# eps_pex.net
KiCad netlist of a schematic drawn in Altium Designer
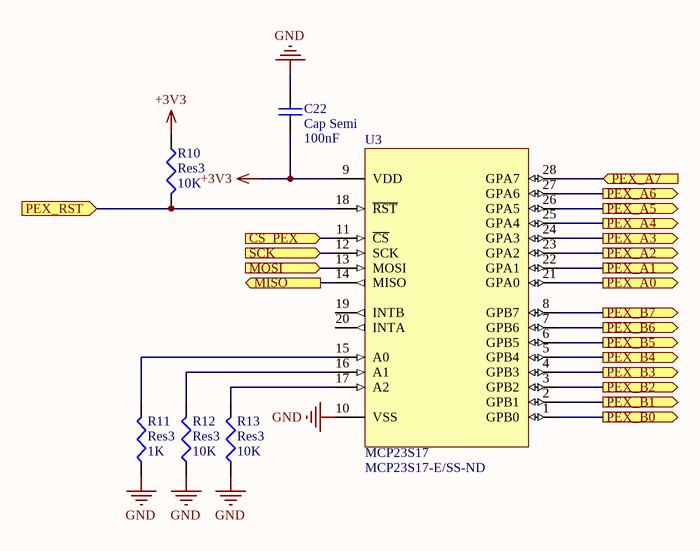
[diagram p0: eps_pex.SchDoc]

(export (version "E")
  (design (tool "Eeschema 10.0.6"))
  (components
    (comp (ref "C22")
      (value "Cap Semi")
      (footprint "1608[0603]")
      (description "Capacitor (Semiconductor SIM Model)")
      (fields (field (name "ALTIUM_VALUE") "100nF") (field (name "PUBLISHER") "Altium Limited"))
      (libsource (lib "Miscellaneous Devices") (part "Cap Semi"))
    )
    (comp (ref "R10")
      (value "Res3")
      (footprint "J1-0603")
      (description "Resistor")
      (fields (field (name "ALTIUM_VALUE") "10K") (field (name "PUBLISHER") "Altium Limited"))
      (libsource (lib "Miscellaneous Devices") (part "Res3"))
    )
    (comp (ref "R11")
      (value "Res3")
      (footprint "J1-0603")
      (description "Resistor")
      (fields (field (name "ALTIUM_VALUE") "1K") (field (name "PUBLISHER") "Altium Limited"))
      (libsource (lib "Miscellaneous Devices") (part "Res3"))
    )
    (comp (ref "R12")
      (value "Res3")
      (footprint "J1-0603")
      (description "Resistor")
      (fields (field (name "ALTIUM_VALUE") "10K") (field (name "PUBLISHER") "Altium Limited"))
      (libsource (lib "Miscellaneous Devices") (part "Res3"))
    )
    (comp (ref "R13")
      (value "Res3")
      (footprint "J1-0603")
      (description "Resistor")
      (fields (field (name "ALTIUM_VALUE") "10K") (field (name "PUBLISHER") "Altium Limited"))
      (libsource (lib "Miscellaneous Devices") (part "Res3"))
    )
    (comp (ref "U3")
      (value "MCP23S17")
      (footprint "SOP65P780X200-28N")
      (description "16 bit I/O expander with SPI interface.")
      (fields (field (name "SUPPLIER PART NUMBER 1") "MCP23S17-E/SS-ND"))
      (libsource (lib "heron-general") (part "MCP23S17"))
    )
  )
  (nets
    (net (code "1") (name "+3V3") (class "Default")
      (node (ref "C22") (pin "2") (pinfunction "2_2") (pintype "passive"))
      (node (ref "R10") (pin "1") (pinfunction "1_1") (pintype "passive"))
      (node (ref "U3") (pin "9") (pinfunction "VDD_9") (pintype "power_in"))
    )
    (net (code "2") (name "/CS_PEX") (class "Default")
      (node (ref "U3") (pin "11") (pinfunction "~{CS}_11") (pintype "input"))
    )
    (net (code "3") (name "/MISO") (class "Default")
      (node (ref "U3") (pin "14") (pinfunction "MISO_14") (pintype "output"))
    )
    (net (code "4") (name "/MOSI") (class "Default")
      (node (ref "U3") (pin "13") (pinfunction "MOSI_13") (pintype "input"))
    )
    (net (code "5") (name "/PEX_A0") (class "Default")
      (node (ref "U3") (pin "21") (pinfunction "GPA0_21") (pintype "bidirectional"))
    )
    (net (code "6") (name "/PEX_A1") (class "Default")
      (node (ref "U3") (pin "22") (pinfunction "GPA1_22") (pintype "bidirectional"))
    )
    (net (code "7") (name "/PEX_A2") (class "Default")
      (node (ref "U3") (pin "23") (pinfunction "GPA2_23") (pintype "bidirectional"))
    )
    (net (code "8") (name "/PEX_A3") (class "Default")
      (node (ref "U3") (pin "24") (pinfunction "GPA3_24") (pintype "bidirectional"))
    )
    (net (code "9") (name "/PEX_A4") (class "Default")
      (node (ref "U3") (pin "25") (pinfunction "GPA4_25") (pintype "bidirectional"))
    )
    (net (code "10") (name "/PEX_A5") (class "Default")
      (node (ref "U3") (pin "26") (pinfunction "GPA5_26") (pintype "bidirectional"))
    )
    (net (code "11") (name "/PEX_A6") (class "Default")
      (node (ref "U3") (pin "27") (pinfunction "GPA6_27") (pintype "bidirectional"))
    )
    (net (code "12") (name "/PEX_A7") (class "Default")
      (node (ref "U3") (pin "28") (pinfunction "GPA7_28") (pintype "bidirectional"))
    )
    (net (code "13") (name "/PEX_B0") (class "Default")
      (node (ref "U3") (pin "1") (pinfunction "GPB0_1") (pintype "bidirectional"))
    )
    (net (code "14") (name "/PEX_B1") (class "Default")
      (node (ref "U3") (pin "2") (pinfunction "GPB1_2") (pintype "bidirectional"))
    )
    (net (code "15") (name "/PEX_B2") (class "Default")
      (node (ref "U3") (pin "3") (pinfunction "GPB2_3") (pintype "bidirectional"))
    )
    (net (code "16") (name "/PEX_B3") (class "Default")
      (node (ref "U3") (pin "4") (pinfunction "GPB3_4") (pintype "bidirectional"))
    )
    (net (code "17") (name "/PEX_B4") (class "Default")
      (node (ref "U3") (pin "5") (pinfunction "GPB4_5") (pintype "bidirectional"))
    )
    (net (code "18") (name "/PEX_B5") (class "Default")
      (node (ref "U3") (pin "6") (pinfunction "GPB5_6") (pintype "bidirectional"))
    )
    (net (code "19") (name "/PEX_B6") (class "Default")
      (node (ref "U3") (pin "7") (pinfunction "GPB6_7") (pintype "bidirectional"))
    )
    (net (code "20") (name "/PEX_B7") (class "Default")
      (node (ref "U3") (pin "8") (pinfunction "GPB7_8") (pintype "bidirectional"))
    )
    (net (code "21") (name "/PEX_RST") (class "Default")
      (node (ref "R10") (pin "2") (pinfunction "2_2") (pintype "passive"))
      (node (ref "U3") (pin "18") (pinfunction "~{RST}_18") (pintype "input"))
    )
    (net (code "22") (name "/SCK") (class "Default")
      (node (ref "U3") (pin "12") (pinfunction "SCK_12") (pintype "input"))
    )
    (net (code "23") (name "GND") (class "Default")
      (node (ref "C22") (pin "1") (pinfunction "1_1") (pintype "passive"))
      (node (ref "R11") (pin "1") (pinfunction "1_1") (pintype "passive"))
      (node (ref "R12") (pin "1") (pinfunction "1_1") (pintype "passive"))
      (node (ref "R13") (pin "1") (pinfunction "1_1") (pintype "passive"))
      (node (ref "U3") (pin "10") (pinfunction "VSS_10") (pintype "power_in"))
    )
    (net (code "24") (name "Net-(U3-A0)") (class "Default")
      (node (ref "R11") (pin "2") (pinfunction "2_2") (pintype "passive"))
      (node (ref "U3") (pin "15") (pinfunction "A0_15") (pintype "input"))
    )
    (net (code "25") (name "Net-(U3-A1)") (class "Default")
      (node (ref "R12") (pin "2") (pinfunction "2_2") (pintype "passive"))
      (node (ref "U3") (pin "16") (pinfunction "A1_16") (pintype "input"))
    )
    (net (code "26") (name "Net-(U3-A2)") (class "Default")
      (node (ref "R13") (pin "2") (pinfunction "2_2") (pintype "passive"))
      (node (ref "U3") (pin "17") (pinfunction "A2_17") (pintype "input"))
    )
    (net (code "27") (name "unconnected-(U3-INTA-Pad20)") (class "Default")
      (node (ref "U3") (pin "20") (pinfunction "INTA_20") (pintype "output"))
    )
    (net (code "28") (name "unconnected-(U3-INTB-Pad19)") (class "Default")
      (node (ref "U3") (pin "19") (pinfunction "INTB_19") (pintype "output"))
    )
  )
)
